# DisplayDrivare.net
KiCad netlist of a schematic drawn in Altium Designer
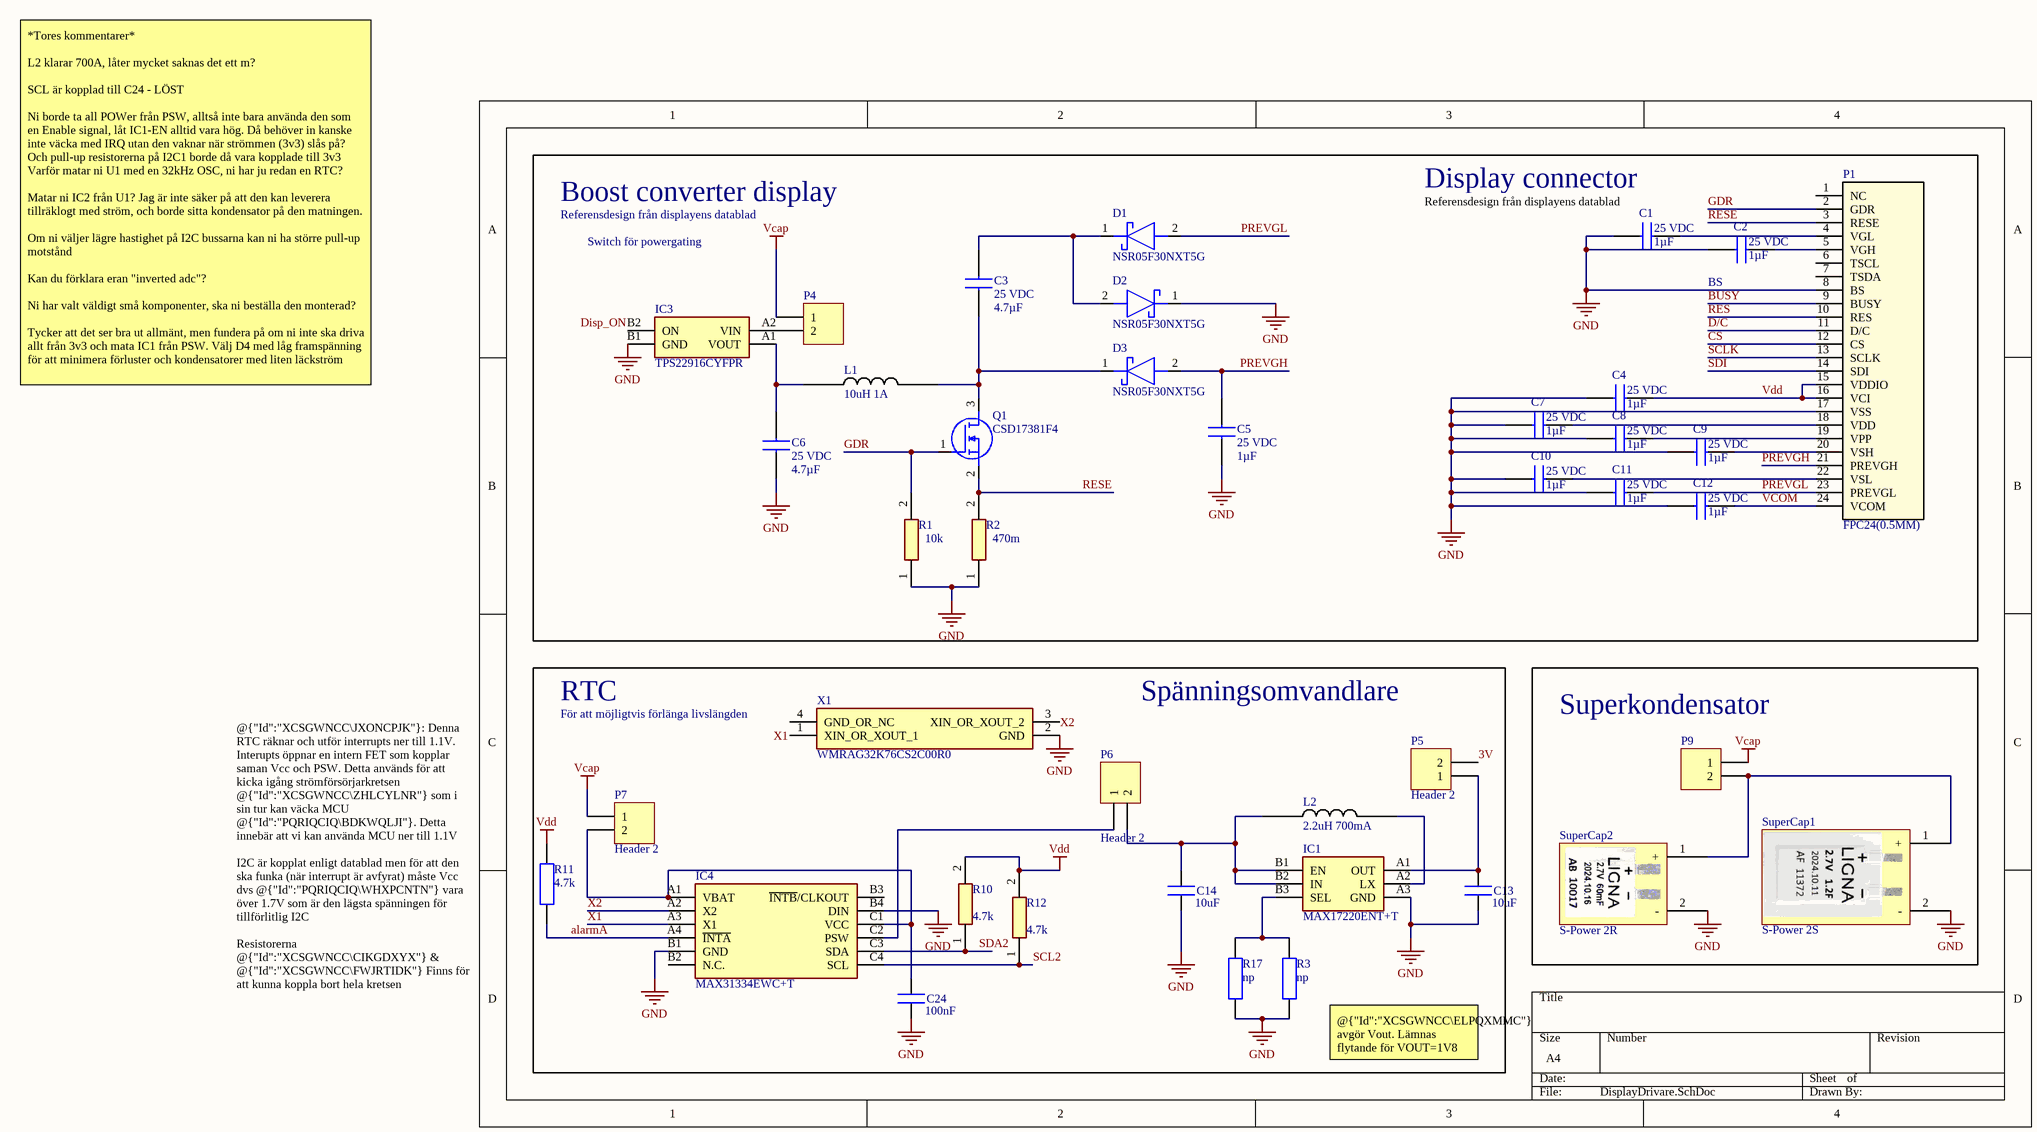
[diagram p0: DisplayDrivare.SchDoc]

(export (version "E")
  (design (tool "Eeschema 10.0.6"))
  (components
    (comp (ref "C1")
      (value "1µF")
      (footprint "CAPC1005X55N")
      (description "Capacitor")
      (fields
        (field (name "RATED VOLTAGE") "25 VDC")
        (field (name "MOUSER PART NUMBER") "81-GRM155R61E105KA2D")
        (field (name "ARROW PART NUMBER") "GRM155R61E105KA12D")
      )
      (libsource (lib "Linköpings Universitet (SE)") (part "GRM155R61E105KA12D"))
    )
    (comp (ref "C2")
      (value "1µF")
      (footprint "CAPC1005X55N")
      (description "Capacitor")
      (fields
        (field (name "RATED VOLTAGE") "25 VDC")
        (field (name "MOUSER PART NUMBER") "81-GRM155R61E105KA2D")
        (field (name "ARROW PART NUMBER") "GRM155R61E105KA12D")
      )
      (libsource (lib "Linköpings Universitet (SE)") (part "GRM155R61E105KA12D"))
    )
    (comp (ref "C3")
      (value "4.7µF")
      (footprint "GRM15x")
      (description "Capacitor")
      (fields
        (field (name "RATED VOLTAGE") "25 VDC")
        (field (name "MOUSER PART NUMBER") "81-GRM15C61E475ME15J")
        (field (name "ARROW PART NUMBER") "GRM155C61E475ME15J")
      )
      (libsource (lib "Linköpings Universitet (SE)") (part "GRM155R61E105KA12D"))
    )
    (comp (ref "C4")
      (value "1µF")
      (footprint "CAPC1005X55N")
      (description "Capacitor")
      (fields
        (field (name "RATED VOLTAGE") "25 VDC")
        (field (name "MOUSER PART NUMBER") "81-GRM155R61E105KA2D")
        (field (name "ARROW PART NUMBER") "GRM155R61E105KA12D")
      )
      (libsource (lib "Linköpings Universitet (SE)") (part "GRM155R61E105KA12D"))
    )
    (comp (ref "C5")
      (value "1µF")
      (footprint "CAPC1005X55N")
      (description "Capacitor")
      (fields
        (field (name "RATED VOLTAGE") "25 VDC")
        (field (name "MOUSER PART NUMBER") "81-GRM155R61E105KA2D")
        (field (name "ARROW PART NUMBER") "GRM155R61E105KA12D")
      )
      (libsource (lib "Linköpings Universitet (SE)") (part "GRM155R61E105KA12D"))
    )
    (comp (ref "C6")
      (value "4.7µF")
      (footprint "GRM15x")
      (description "Capacitor")
      (fields
        (field (name "RATED VOLTAGE") "25 VDC")
        (field (name "MOUSER PART NUMBER") "81-GRM15C61E475ME15J")
        (field (name "ARROW PART NUMBER") "GRM155C61E475ME15J")
      )
      (libsource (lib "Linköpings Universitet (SE)") (part "GRM155R61E105KA12D"))
    )
    (comp (ref "C7")
      (value "1µF")
      (footprint "CAPC1005X55N")
      (description "Capacitor")
      (fields
        (field (name "RATED VOLTAGE") "25 VDC")
        (field (name "MOUSER PART NUMBER") "81-GRM155R61E105KA2D")
        (field (name "ARROW PART NUMBER") "GRM155R61E105KA12D")
      )
      (libsource (lib "Linköpings Universitet (SE)") (part "GRM155R61E105KA12D"))
    )
    (comp (ref "C8")
      (value "1µF")
      (footprint "CAPC1005X55N")
      (description "Capacitor")
      (fields
        (field (name "RATED VOLTAGE") "25 VDC")
        (field (name "MOUSER PART NUMBER") "81-GRM155R61E105KA2D")
        (field (name "ARROW PART NUMBER") "GRM155R61E105KA12D")
      )
      (libsource (lib "Linköpings Universitet (SE)") (part "GRM155R61E105KA12D"))
    )
    (comp (ref "C9")
      (value "1µF")
      (footprint "CAPC1005X55N")
      (description "Capacitor")
      (fields
        (field (name "RATED VOLTAGE") "25 VDC")
        (field (name "MOUSER PART NUMBER") "81-GRM155R61E105KA2D")
        (field (name "ARROW PART NUMBER") "GRM155R61E105KA12D")
      )
      (libsource (lib "Linköpings Universitet (SE)") (part "GRM155R61E105KA12D"))
    )
    (comp (ref "C10")
      (value "1µF")
      (footprint "CAPC1005X55N")
      (description "Capacitor")
      (fields
        (field (name "RATED VOLTAGE") "25 VDC")
        (field (name "MOUSER PART NUMBER") "81-GRM155R61E105KA2D")
        (field (name "ARROW PART NUMBER") "GRM155R61E105KA12D")
      )
      (libsource (lib "Linköpings Universitet (SE)") (part "GRM155R61E105KA12D"))
    )
    (comp (ref "C11")
      (value "1µF")
      (footprint "CAPC1005X55N")
      (description "Capacitor")
      (fields
        (field (name "RATED VOLTAGE") "25 VDC")
        (field (name "MOUSER PART NUMBER") "81-GRM155R61E105KA2D")
        (field (name "ARROW PART NUMBER") "GRM155R61E105KA12D")
      )
      (libsource (lib "Linköpings Universitet (SE)") (part "GRM155R61E105KA12D"))
    )
    (comp (ref "C12")
      (value "1µF")
      (footprint "CAPC1005X55N")
      (description "Capacitor")
      (fields
        (field (name "RATED VOLTAGE") "25 VDC")
        (field (name "MOUSER PART NUMBER") "81-GRM155R61E105KA2D")
        (field (name "ARROW PART NUMBER") "GRM155R61E105KA12D")
      )
      (libsource (lib "Linköpings Universitet (SE)") (part "GRM155R61E105KA12D"))
    )
    (comp (ref "C13")
      (value "AMK105CBJ106MV-F")
      (footprint "CAPC1005X70N")
      (description "Multilayer Ceramic Capacitors MLCC - SMD/SMT 4V 10uF X5R 0402 20 %")
      (fields (field (name "CAPACITANCE") "10uF"))
      (libsource (lib "Schlib") (part "Generic capacitor"))
    )
    (comp (ref "C14")
      (value "AMK105CBJ106MV-F")
      (footprint "CAPC1005X70N")
      (description "Multilayer Ceramic Capacitors MLCC - SMD/SMT 4V 10uF X5R 0402 20 %")
      (fields (field (name "CAPACITANCE") "10uF"))
      (libsource (lib "Schlib") (part "Generic capacitor"))
    )
    (comp (ref "C24")
      (value "MCAST105SB5104KFNA01")
      (footprint "CAPC1005X70N")
      (description "Multilayer Ceramic Capacitors MLCC - SMD/SMT 25V 0.1uF X5R 0402 10% Medical")
      (fields (field (name "CAPACITANCE") "100nF"))
      (libsource (lib "Schlib") (part "Generic capacitor"))
    )
    (comp (ref "D1")
      (value "NSR05F30NXT5G")
      (footprint "NSR05F30NXT5G")
      (description "Schottky Diode")
      (fields (field (name "MOUSER PART NUMBER") "863-NSR05F30NXT5G"))
      (libsource (lib "Linköpings Universitet (SE)") (part "NSR05F30NXT5G"))
    )
    (comp (ref "D2")
      (value "NSR05F30NXT5G")
      (footprint "NSR05F30NXT5G")
      (description "Schottky Diode")
      (fields (field (name "MOUSER PART NUMBER") "863-NSR05F30NXT5G"))
      (libsource (lib "Linköpings Universitet (SE)") (part "NSR05F30NXT5G"))
    )
    (comp (ref "D3")
      (value "NSR05F30NXT5G")
      (footprint "NSR05F30NXT5G")
      (description "Schottky Diode")
      (fields (field (name "MOUSER PART NUMBER") "863-NSR05F30NXT5G"))
      (libsource (lib "Linköpings Universitet (SE)") (part "NSR05F30NXT5G"))
    )
    (comp (ref "IC1")
      (value "MAX17220ENT+T")
      (footprint "BGA6C40P3X2_142X89X50")
      (description "MAXIM INTEGRATED PRODUCTS - MAX17220ENT+T - DC-DC Switching Step Up Regulator")
      (fields (field (name "MOUSER PART NUMBER") "700-MAX17220ENT+T"))
      (libsource (lib "Linköpings Universitet (SE)") (part "MAX17220ENT+T"))
    )
    (comp (ref "IC3")
      (value "TPS22916CYFPR")
      (footprint "BGA4C40P2X2_78X78X50")
      (description "TPS22916 5.5-V")
      (fields (field (name "MOUSER PART NUMBER") "595-TPS22916CYFPR"))
      (libsource (lib "Linköpings Universitet (SE)") (part "TPS22916CYFPR"))
    )
    (comp (ref "IC4")
      (value "MAX31334EWC+T")
      (footprint "BGA12C50P4X3_197X147X69")
      (description "Ultra-Low-Power Real Time Clock with Integrated Power Switch")
      (fields (field (name "MOUSER PART NUMBER") "700-MAX31334EWC+T"))
      (libsource (lib "Linköpings Universitet (SE)") (part "MAX31334EWC+T"))
    )
    (comp (ref "L1")
      (value "SRP0408F-100M")
      (footprint "INDPM4341X80N")
      (description "Power Inductors - SMD 10 UH 20%")
      (fields (field (name "RATING") "10uH 1A"))
      (libsource (lib "Linköpings Universitet (SE)") (part "SRP0408F-100M"))
    )
    (comp (ref "L2")
      (value "74479774222")
      (footprint "WE-PMI_080562")
      (description "Inductor-WE")
      (fields (field (name "RATING") "2.2uH 700mA"))
      (libsource (lib "Linköpings Universitet (SE)") (part "SRP0408F-100M"))
    )
    (comp (ref "P1")
      (value "FPC24(0.5MM)")
      (footprint "FPC24 (0.5mm)")
      (description "No Description Available")
      (libsource (lib "5034802400") (part "FPC24(0.5MM)"))
    )
    (comp (ref "P4")
      (value "Header 2")
      (footprint "HDR1X2")
      (description "Header, 2-Pin")
      (fields (field (name "PUBLISHER") "Altium Limited"))
      (libsource (lib "Linköpings Universitet (SE)") (part "Header 2H"))
    )
    (comp (ref "P5")
      (value "Header 2")
      (footprint "HDR1X2")
      (description "Header, 2-Pin")
      (fields (field (name "PUBLISHER") "Altium Limited"))
      (libsource (lib "") (part "Header 2H_2"))
    )
    (comp (ref "P6")
      (value "Header 2")
      (footprint "HDR1X2")
      (description "Header, 2-Pin")
      (fields (field (name "PUBLISHER") "Altium Limited"))
      (libsource (lib "") (part "Header 2H_3"))
    )
    (comp (ref "P7")
      (value "Header 2")
      (footprint "HDR1X2")
      (description "Header, 2-Pin")
      (fields (field (name "PUBLISHER") "Altium Limited"))
      (libsource (lib "Linköpings Universitet (SE)") (part "Header 2H"))
    )
    (comp (ref "P9")
      (value "Header 2")
      (footprint "HDR1X2")
      (description "Header, 2-Pin")
      (fields (field (name "PUBLISHER") "Altium Limited"))
      (libsource (lib "") (part "Header 2H_1"))
    )
    (comp (ref "Q1")
      (value "CSD17381F4")
      (footprint "CSD17381F4")
      (description "MOSFET (N-Channel)")
      (fields (field (name "MOUSER PART NUMBER") "595-CSD17381F4"))
      (libsource (lib "Linköpings Universitet (SE)") (part "Si1308EDL-T1-GE3"))
    )
    (comp (ref "R1")
      (value "CRCW040210K0FKEDHP")
      (footprint "RESC1005X40N")
      (fields (field (name "MOUSER PART NUMBER") "71-CRCW040210K0FKEDH") (field (name "RESISTANCE") "10k"))
      (libsource (lib "Linköpings Universitet (SE)") (part "CRCW040210K0FKEDHP"))
    )
    (comp (ref "R2")
      (value "ERJ-U6QJR47V")
      (footprint "RESC2012X65N")
      (description "Thick Film Resistors - SMD 0805 0.25W 5% .47ohms AEC-Q200")
      (fields (field (name "MOUSER PART NUMBER") "667-ERJ-U6QJR47V") (field (name "RESISTANCE") "470m"))
      (libsource (lib "Linköpings Universitet (SE)") (part "CRCW040210K0FKEDHP"))
    )
    (comp (ref "R3")
      (value "CRT0402-BY-80R6GLF")
      (footprint "RESC1005X40N")
      (description "Thin Film Resistors 1/16watts 80.6 ohm 0.10%")
      (fields (field (name "RESISTANCE") "np"))
      (libsource (lib "Schlib") (part "Generic resistor"))
    )
    (comp (ref "R10")
      (value "CRCW04024K70FKEDHP")
      (footprint "RESC1005X40N")
      (fields (field (name "MOUSER PART NUMBER") "71-CRCW04024K70FKEDH") (field (name "RESISTANCE") "4.7k"))
      (libsource (lib "Linköpings Universitet (SE)") (part "CRCW04024K70FKEDHP"))
    )
    (comp (ref "R11")
      (value "CRCW04024K70FKEDHP")
      (footprint "RESC1005X40N")
      (fields (field (name "RESISTANCE") "4.7k"))
      (libsource (lib "") (part "Generic resistor_1"))
    )
    (comp (ref "R12")
      (value "CRCW04024K70FKEDHP")
      (footprint "RESC1005X40N")
      (fields (field (name "MOUSER PART NUMBER") "71-CRCW04024K70FKEDH") (field (name "RESISTANCE") "4.7k"))
      (libsource (lib "Linköpings Universitet (SE)") (part "CRCW04024K70FKEDHP"))
    )
    (comp (ref "R17")
      (value "CRT0402-BY-80R6GLF")
      (footprint "RESC1005X40N")
      (description "Thin Film Resistors 1/16watts 80.6 ohm 0.10%")
      (fields (field (name "RESISTANCE") "np"))
      (libsource (lib "Schlib") (part "Generic resistor"))
    )
    (comp (ref "SuperCap1")
      (value "S-Power 2S")
      (footprint "S-Power 2S")
      (libsource (lib "Linköpings Universitet (SE)") (part "S-Power 2S"))
    )
    (comp (ref "SuperCap2")
      (value "S-Power 2R")
      (footprint "S-Power 2R")
      (libsource (lib "Linköpings Universitet (SE)") (part "S-Power 2R"))
    )
    (comp (ref "X1")
      (value "WMRAG32K76CS2C00R0")
      (footprint "WMRAG32K76CS2C00R0")
      (description "32.768 kHz +/-20ppm Crystal 8pF 75 kOhms 4-SMD")
      (fields (field (name "MOUSER PART NUMBER") "81-WMRAG32K76CS2C00R"))
      (libsource (lib "Linköpings Universitet (SE)") (part "WMRAG32K76CS2C00R0"))
    )
  )
  (nets
    (net (code "1") (name "/3V") (class "Default")
      (node (ref "P5") (pin "2") (pinfunction "2_2") (pintype "passive"))
    )
    (net (code "2") (name "/BUSY") (class "Default")
      (node (ref "P1") (pin "9") (pinfunction "BUSY_9") (pintype "passive"))
    )
    (net (code "3") (name "/CS") (class "Default")
      (node (ref "P1") (pin "12") (pinfunction "CS_12") (pintype "passive"))
    )
    (net (code "4") (name "/Disp_ON") (class "Default")
      (node (ref "IC3") (pin "B2") (pinfunction "ON_B2") (pintype "passive"))
    )
    (net (code "5") (name "/D{slash}C") (class "Default")
      (node (ref "P1") (pin "11") (pinfunction "D/C_11") (pintype "passive"))
    )
    (net (code "6") (name "/GDR") (class "Default")
      (node (ref "P1") (pin "2") (pinfunction "GDR_2") (pintype "passive"))
      (node (ref "Q1") (pin "1") (pinfunction "G_1") (pintype "passive"))
      (node (ref "R1") (pin "2") (pinfunction "2_2") (pintype "passive"))
    )
    (net (code "7") (name "/PREVGH") (class "Default")
      (node (ref "C5") (pin "2") (pinfunction "2_2") (pintype "passive"))
      (node (ref "D3") (pin "2") (pinfunction "A_2") (pintype "passive"))
      (node (ref "P1") (pin "21") (pinfunction "PREVGH_21") (pintype "passive"))
    )
    (net (code "8") (name "/PREVGL") (class "Default")
      (node (ref "C11") (pin "1") (pinfunction "1_1") (pintype "passive"))
      (node (ref "D1") (pin "2") (pinfunction "A_2") (pintype "passive"))
      (node (ref "P1") (pin "23") (pinfunction "PREVGL_23") (pintype "passive"))
    )
    (net (code "9") (name "/RES") (class "Default")
      (node (ref "P1") (pin "10") (pinfunction "RES_10") (pintype "passive"))
    )
    (net (code "10") (name "/RESE") (class "Default")
      (node (ref "P1") (pin "3") (pinfunction "RESE_3") (pintype "passive"))
      (node (ref "Q1") (pin "2") (pinfunction "S_2") (pintype "passive"))
      (node (ref "R2") (pin "2") (pinfunction "2_2") (pintype "passive"))
    )
    (net (code "11") (name "/SCL2") (class "Default")
      (node (ref "IC4") (pin "C4") (pinfunction "SCL_C4") (pintype "passive"))
      (node (ref "R12") (pin "1") (pinfunction "1_1") (pintype "passive"))
    )
    (net (code "12") (name "/SCLK") (class "Default")
      (node (ref "P1") (pin "13") (pinfunction "SCLK_13") (pintype "passive"))
    )
    (net (code "13") (name "/SDA2") (class "Default")
      (node (ref "IC4") (pin "C3") (pinfunction "SDA_C3") (pintype "passive"))
      (node (ref "R10") (pin "1") (pinfunction "1_1") (pintype "passive"))
    )
    (net (code "14") (name "/SDI") (class "Default")
      (node (ref "P1") (pin "14") (pinfunction "SDI_14") (pintype "passive"))
    )
    (net (code "15") (name "/VCOM") (class "Default")
      (node (ref "C12") (pin "1") (pinfunction "1_1") (pintype "passive"))
      (node (ref "P1") (pin "24") (pinfunction "VCOM_24") (pintype "passive"))
    )
    (net (code "16") (name "/X1") (class "Default")
      (node (ref "IC4") (pin "A3") (pinfunction "X1_A3") (pintype "passive"))
      (node (ref "X1") (pin "1") (pinfunction "XIN_OR_XOUT_1_1") (pintype "passive"))
    )
    (net (code "17") (name "/X2") (class "Default")
      (node (ref "IC4") (pin "A2") (pinfunction "X2_A2") (pintype "passive"))
      (node (ref "X1") (pin "3") (pinfunction "XIN_OR_XOUT_2_3") (pintype "passive"))
    )
    (net (code "18") (name "/alarmA") (class "Default")
      (node (ref "IC4") (pin "A4") (pinfunction "~{INTA}_A4") (pintype "passive"))
      (node (ref "R11") (pin "2") (pinfunction "2_2") (pintype "passive"))
    )
    (net (code "19") (name "GND") (class "Default")
      (node (ref "C1") (pin "2") (pinfunction "2_2") (pintype "passive"))
      (node (ref "C10") (pin "2") (pinfunction "2_2") (pintype "passive"))
      (node (ref "C11") (pin "2") (pinfunction "2_2") (pintype "passive"))
      (node (ref "C12") (pin "2") (pinfunction "2_2") (pintype "passive"))
      (node (ref "C13") (pin "1") (pinfunction "1_1") (pintype "passive"))
      (node (ref "C14") (pin "1") (pinfunction "1_1") (pintype "passive"))
      (node (ref "C2") (pin "2") (pinfunction "2_2") (pintype "passive"))
      (node (ref "C24") (pin "2") (pinfunction "2_2") (pintype "passive"))
      (node (ref "C4") (pin "2") (pinfunction "2_2") (pintype "passive"))
      (node (ref "C5") (pin "1") (pinfunction "1_1") (pintype "passive"))
      (node (ref "C6") (pin "1") (pinfunction "1_1") (pintype "passive"))
      (node (ref "C7") (pin "2") (pinfunction "2_2") (pintype "passive"))
      (node (ref "C8") (pin "2") (pinfunction "2_2") (pintype "passive"))
      (node (ref "C9") (pin "2") (pinfunction "2_2") (pintype "passive"))
      (node (ref "D2") (pin "1") (pinfunction "K_1") (pintype "passive"))
      (node (ref "IC1") (pin "A3") (pinfunction "GND_A3") (pintype "passive"))
      (node (ref "IC3") (pin "B1") (pinfunction "GND_B1") (pintype "passive"))
      (node (ref "IC4") (pin "B1") (pinfunction "GND_B1") (pintype "passive"))
      (node (ref "IC4") (pin "B4") (pinfunction "DIN_B4") (pintype "passive"))
      (node (ref "P1") (pin "17") (pinfunction "VSS_17") (pintype "passive"))
      (node (ref "P1") (pin "8") (pinfunction "BS_8") (pintype "passive"))
      (node (ref "R1") (pin "1") (pinfunction "1_1") (pintype "passive"))
      (node (ref "R17") (pin "1") (pinfunction "1_1") (pintype "passive"))
      (node (ref "R2") (pin "1") (pinfunction "1_1") (pintype "passive"))
      (node (ref "R3") (pin "1") (pinfunction "1_1") (pintype "passive"))
      (node (ref "SuperCap1") (pin "2") (pinfunction "-_2") (pintype "passive"))
      (node (ref "SuperCap2") (pin "2") (pinfunction "-_2") (pintype "passive"))
      (node (ref "X1") (pin "2") (pinfunction "GND_2") (pintype "passive"))
    )
    (net (code "20") (name "Net-(D1-K)") (class "Default")
      (node (ref "C3") (pin "2") (pinfunction "2_2") (pintype "passive"))
      (node (ref "D1") (pin "1") (pinfunction "K_1") (pintype "passive"))
      (node (ref "D2") (pin "2") (pinfunction "A_2") (pintype "passive"))
    )
    (net (code "21") (name "Net-(D3-K)") (class "Default")
      (node (ref "C3") (pin "1") (pinfunction "1_1") (pintype "passive"))
      (node (ref "D3") (pin "1") (pinfunction "K_1") (pintype "passive"))
      (node (ref "L1") (pin "2") (pinfunction "2_2") (pintype "passive"))
      (node (ref "Q1") (pin "3") (pinfunction "D_3") (pintype "passive"))
    )
    (net (code "22") (name "Net-(IC1-EN)") (class "Default")
      (node (ref "C14") (pin "2") (pinfunction "2_2") (pintype "passive"))
      (node (ref "IC1") (pin "B1") (pinfunction "EN_B1") (pintype "passive"))
      (node (ref "IC1") (pin "B2") (pinfunction "IN_B2") (pintype "passive"))
      (node (ref "L2") (pin "1") (pinfunction "1_1") (pintype "passive"))
      (node (ref "P6") (pin "2") (pinfunction "2_2") (pintype "passive"))
    )
    (net (code "23") (name "Net-(IC1-LX)") (class "Default")
      (node (ref "IC1") (pin "A2") (pinfunction "LX_A2") (pintype "passive"))
      (node (ref "L2") (pin "2") (pinfunction "2_2") (pintype "passive"))
    )
    (net (code "24") (name "Net-(IC1-OUT)") (class "Default")
      (node (ref "C13") (pin "2") (pinfunction "2_2") (pintype "passive"))
      (node (ref "IC1") (pin "A1") (pinfunction "OUT_A1") (pintype "passive"))
      (node (ref "P5") (pin "1") (pinfunction "1_1") (pintype "passive"))
    )
    (net (code "25") (name "Net-(IC1-SEL)") (class "Default")
      (node (ref "IC1") (pin "B3") (pinfunction "SEL_B3") (pintype "passive"))
      (node (ref "R17") (pin "2") (pinfunction "2_2") (pintype "passive"))
      (node (ref "R3") (pin "2") (pinfunction "2_2") (pintype "passive"))
    )
    (net (code "26") (name "Net-(IC3-VIN)") (class "Default")
      (node (ref "IC3") (pin "A2") (pinfunction "VIN_A2") (pintype "passive"))
      (node (ref "P4") (pin "2") (pinfunction "2_2") (pintype "passive"))
    )
    (net (code "27") (name "Net-(IC3-VOUT)") (class "Default")
      (node (ref "C6") (pin "2") (pinfunction "2_2") (pintype "passive"))
      (node (ref "IC3") (pin "A1") (pinfunction "VOUT_A1") (pintype "passive"))
      (node (ref "L1") (pin "1") (pinfunction "1_1") (pintype "passive"))
    )
    (net (code "28") (name "Net-(IC4-PSW)") (class "Default")
      (node (ref "IC4") (pin "C2") (pinfunction "PSW_C2") (pintype "passive"))
      (node (ref "P6") (pin "1") (pinfunction "1_1") (pintype "passive"))
    )
    (net (code "29") (name "Net-(IC4-VBAT)") (class "Default")
      (node (ref "C24") (pin "1") (pinfunction "1_1") (pintype "passive"))
      (node (ref "IC4") (pin "A1") (pinfunction "VBAT_A1") (pintype "passive"))
      (node (ref "IC4") (pin "C1") (pinfunction "VCC_C1") (pintype "passive"))
      (node (ref "P7") (pin "2") (pinfunction "2_2") (pintype "passive"))
    )
    (net (code "30") (name "Net-(P1-VDD)") (class "Default")
      (node (ref "C7") (pin "1") (pinfunction "1_1") (pintype "passive"))
      (node (ref "P1") (pin "18") (pinfunction "VDD_18") (pintype "passive"))
    )
    (net (code "31") (name "Net-(P1-VGH)") (class "Default")
      (node (ref "C2") (pin "1") (pinfunction "1_1") (pintype "passive"))
      (node (ref "P1") (pin "5") (pinfunction "VGH_5") (pintype "passive"))
    )
    (net (code "32") (name "Net-(P1-VGL)") (class "Default")
      (node (ref "C1") (pin "1") (pinfunction "1_1") (pintype "passive"))
      (node (ref "P1") (pin "4") (pinfunction "VGL_4") (pintype "passive"))
    )
    (net (code "33") (name "Net-(P1-VPP)") (class "Default")
      (node (ref "C8") (pin "1") (pinfunction "1_1") (pintype "passive"))
      (node (ref "P1") (pin "19") (pinfunction "VPP_19") (pintype "passive"))
    )
    (net (code "34") (name "Net-(P1-VSH)") (class "Default")
      (node (ref "C9") (pin "1") (pinfunction "1_1") (pintype "passive"))
      (node (ref "P1") (pin "20") (pinfunction "VSH_20") (pintype "passive"))
    )
    (net (code "35") (name "Net-(P1-VSL)") (class "Default")
      (node (ref "C10") (pin "1") (pinfunction "1_1") (pintype "passive"))
      (node (ref "P1") (pin "22") (pinfunction "VSL_22") (pintype "passive"))
    )
    (net (code "36") (name "Net-(SuperCap1-+)") (class "Default")
      (node (ref "P9") (pin "2") (pinfunction "2_2") (pintype "passive"))
      (node (ref "SuperCap1") (pin "1") (pinfunction "+_1") (pintype "passive"))
      (node (ref "SuperCap2") (pin "1") (pinfunction "+_1") (pintype "passive"))
    )
    (net (code "37") (name "Vcap") (class "Default")
      (node (ref "P4") (pin "1") (pinfunction "1_1") (pintype "passive"))
      (node (ref "P7") (pin "1") (pinfunction "1_1") (pintype "passive"))
      (node (ref "P9") (pin "1") (pinfunction "1_1") (pintype "passive"))
    )
    (net (code "38") (name "Vdd") (class "Default")
      (node (ref "C4") (pin "1") (pinfunction "1_1") (pintype "passive"))
      (node (ref "P1") (pin "15") (pinfunction "VDDIO_15") (pintype "passive"))
      (node (ref "P1") (pin "16") (pinfunction "VCI_16") (pintype "passive"))
      (node (ref "R10") (pin "2") (pinfunction "2_2") (pintype "passive"))
      (node (ref "R11") (pin "1") (pinfunction "1_1") (pintype "passive"))
      (node (ref "R12") (pin "2") (pinfunction "2_2") (pintype "passive"))
    )
    (net (code "39") (name "unconnected-(IC4-N.C.-PadB2)") (class "Default")
      (node (ref "IC4") (pin "B2") (pinfunction "N.C._B2") (pintype "passive"))
    )
    (net (code "40") (name "unconnected-(IC4-~{INTB}{slash}CLKOUT-PadB3)") (class "Default")
      (node (ref "IC4") (pin "B3") (pinfunction "~{INTB}/CLKOUT_B3") (pintype "passive"))
    )
    (net (code "41") (name "unconnected-(P1-NC-Pad1)") (class "Default")
      (node (ref "P1") (pin "1") (pinfunction "NC_1") (pintype "passive"))
    )
    (net (code "42") (name "unconnected-(P1-TSCL-Pad6)") (class "Default")
      (node (ref "P1") (pin "6") (pinfunction "TSCL_6") (pintype "passive"))
    )
    (net (code "43") (name "unconnected-(P1-TSDA-Pad7)") (class "Default")
      (node (ref "P1") (pin "7") (pinfunction "TSDA_7") (pintype "passive"))
    )
    (net (code "44") (name "unconnected-(X1-GND_OR_NC-Pad4)") (class "Default")
      (node (ref "X1") (pin "4") (pinfunction "GND_OR_NC_4") (pintype "passive"))
    )
  )
)
